# power_board.net
KiCad netlist of a schematic drawn in EAGLE
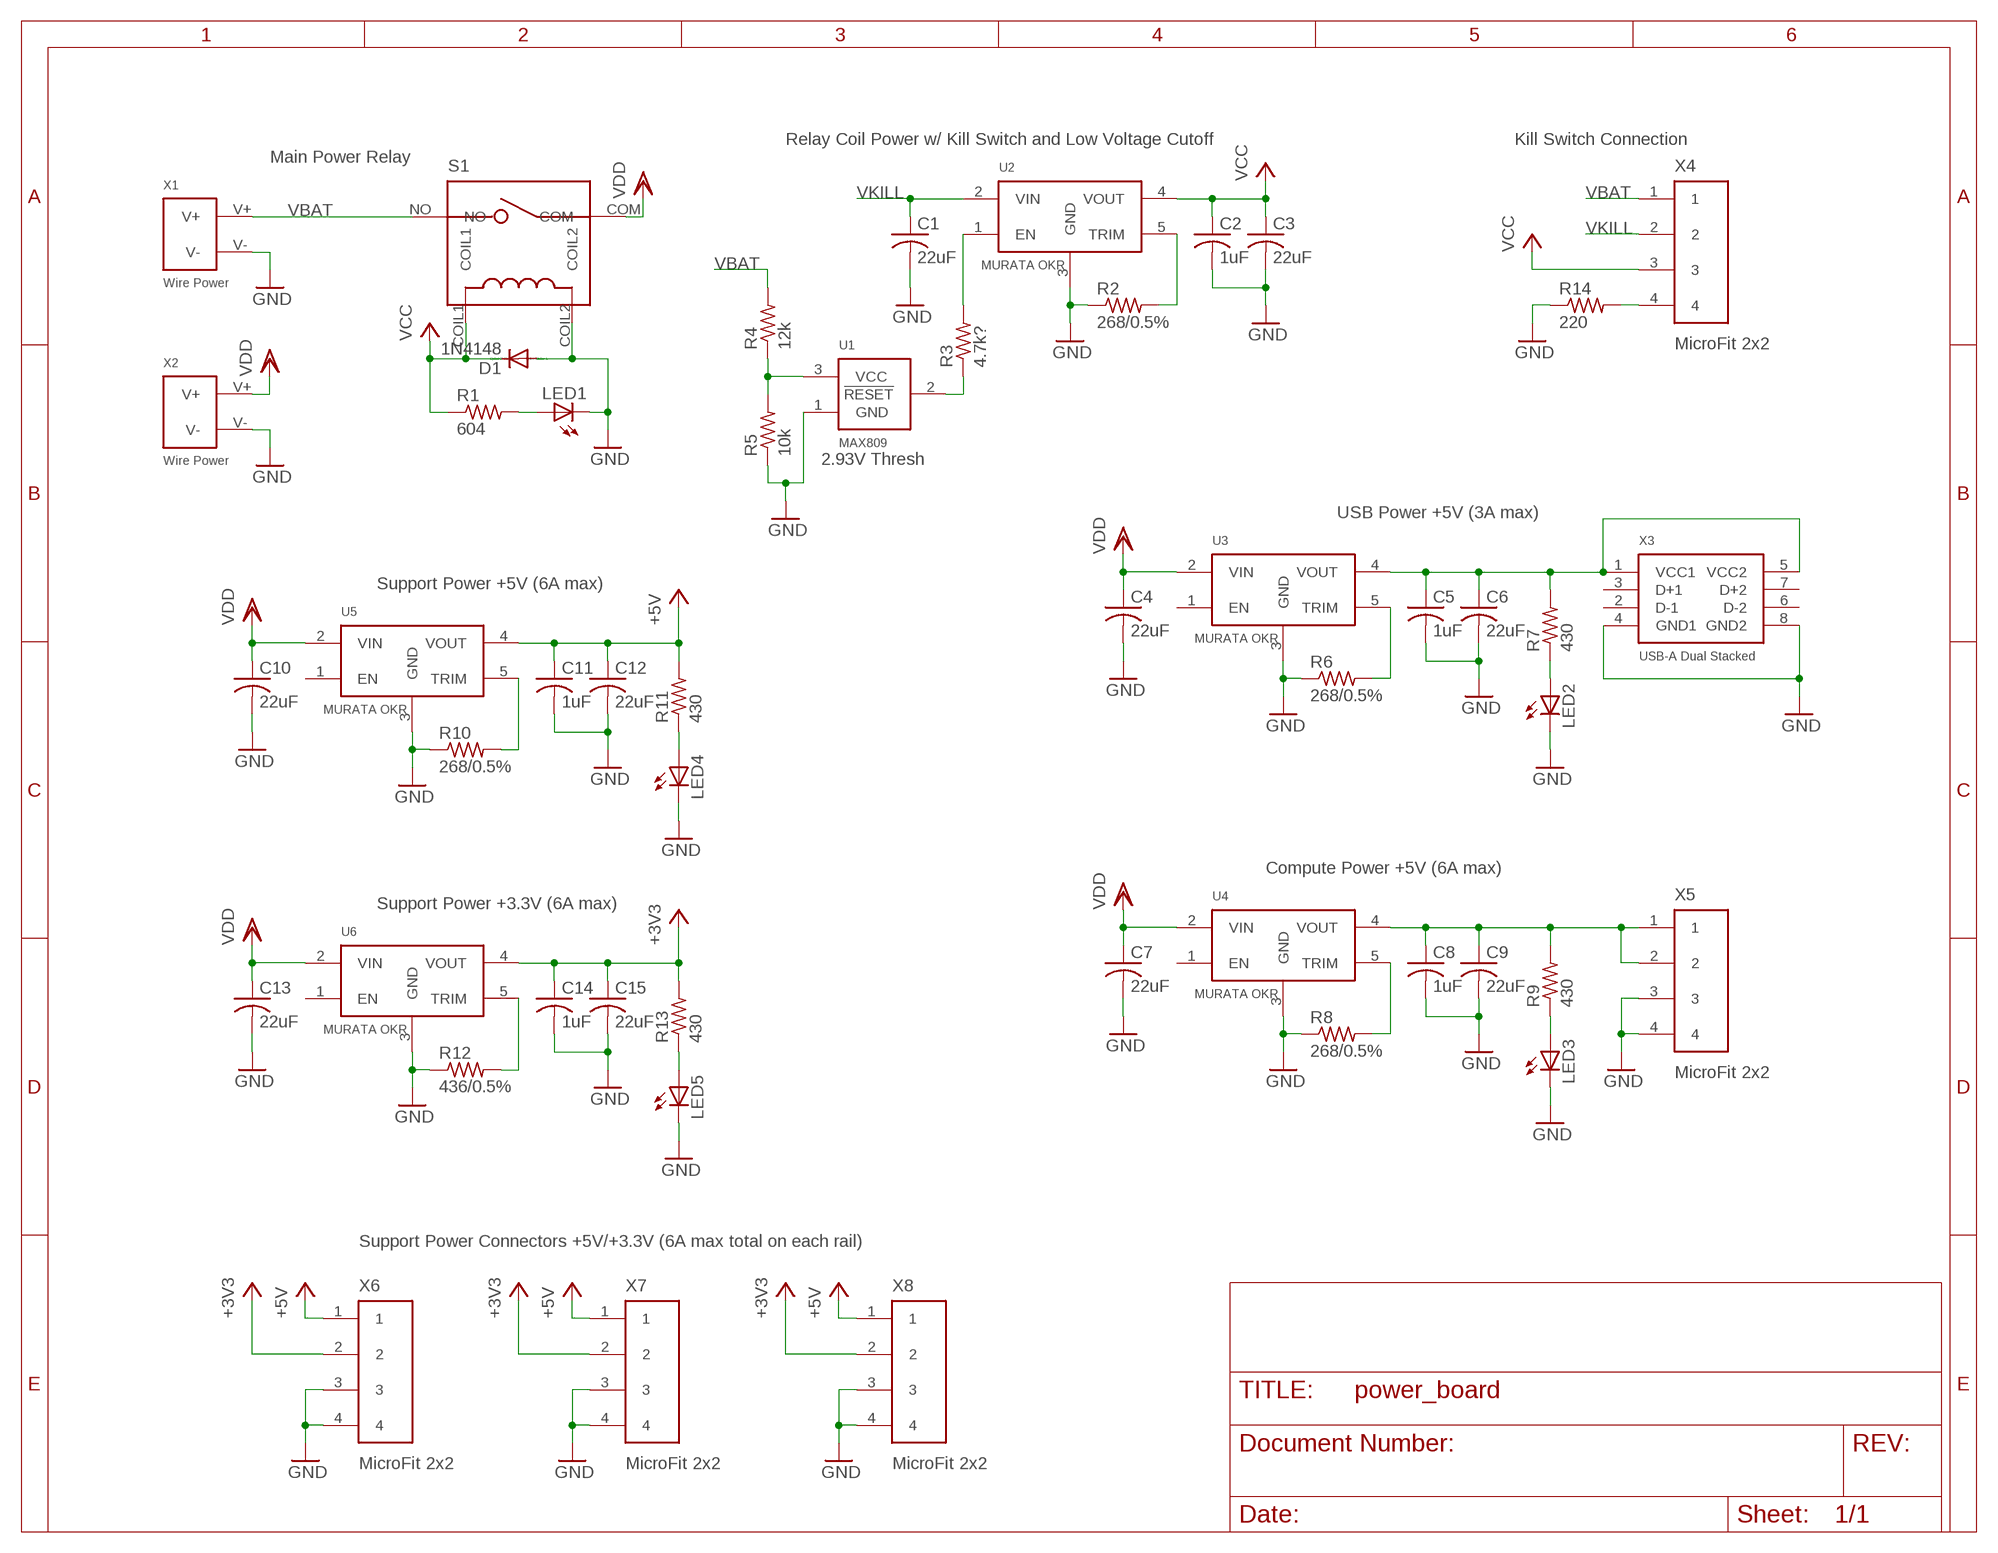
[diagram p0: schematic, sheet 1]

(export (version "E")
  (design (tool "Eeschema 10.0.6"))
  (components
    (comp (ref "C1")
      (value "22uF")
      (footprint "eagle-import:C1210")
      (libsource (lib "eagle-import") (part "C-USC1210"))
    )
    (comp (ref "C2")
      (value "1uF")
      (footprint "eagle-import:C1210")
      (libsource (lib "eagle-import") (part "C-USC1210"))
    )
    (comp (ref "C3")
      (value "22uF")
      (footprint "eagle-import:C1210")
      (libsource (lib "eagle-import") (part "C-USC1210"))
    )
    (comp (ref "C4")
      (value "22uF")
      (footprint "eagle-import:C1210")
      (libsource (lib "eagle-import") (part "C-USC1210"))
    )
    (comp (ref "C5")
      (value "1uF")
      (footprint "eagle-import:C1210")
      (libsource (lib "eagle-import") (part "C-USC1210"))
    )
    (comp (ref "C6")
      (value "22uF")
      (footprint "eagle-import:C1210")
      (libsource (lib "eagle-import") (part "C-USC1210"))
    )
    (comp (ref "C7")
      (value "22uF")
      (footprint "eagle-import:C1210")
      (libsource (lib "eagle-import") (part "C-USC1210"))
    )
    (comp (ref "C8")
      (value "1uF")
      (footprint "eagle-import:C1210")
      (libsource (lib "eagle-import") (part "C-USC1210"))
    )
    (comp (ref "C9")
      (value "22uF")
      (footprint "eagle-import:C1210")
      (libsource (lib "eagle-import") (part "C-USC1210"))
    )
    (comp (ref "C10")
      (value "22uF")
      (footprint "eagle-import:C1210")
      (libsource (lib "eagle-import") (part "C-USC1210"))
    )
    (comp (ref "C11")
      (value "1uF")
      (footprint "eagle-import:C1210")
      (libsource (lib "eagle-import") (part "C-USC1210"))
    )
    (comp (ref "C12")
      (value "22uF")
      (footprint "eagle-import:C1210")
      (libsource (lib "eagle-import") (part "C-USC1210"))
    )
    (comp (ref "C13")
      (value "22uF")
      (footprint "eagle-import:C1210")
      (libsource (lib "eagle-import") (part "C-USC1210"))
    )
    (comp (ref "C14")
      (value "1uF")
      (footprint "eagle-import:C1210")
      (libsource (lib "eagle-import") (part "C-USC1210"))
    )
    (comp (ref "C15")
      (value "22uF")
      (footprint "eagle-import:C1210")
      (libsource (lib "eagle-import") (part "C-USC1210"))
    )
    (comp (ref "D1")
      (value "1N4148")
      (footprint "eagle-import:SOD123")
      (libsource (lib "eagle-import") (part "DIODE-SOD123"))
    )
    (comp (ref "LED1")
      (value "LEDCHIPLED_0603")
      (footprint "eagle-import:CHIPLED_0603")
      (libsource (lib "eagle-import") (part "LEDCHIPLED_0603"))
    )
    (comp (ref "LED2")
      (value "LEDCHIPLED_0603")
      (footprint "eagle-import:CHIPLED_0603")
      (libsource (lib "eagle-import") (part "LEDCHIPLED_0603"))
    )
    (comp (ref "LED3")
      (value "LEDCHIPLED_0603")
      (footprint "eagle-import:CHIPLED_0603")
      (libsource (lib "eagle-import") (part "LEDCHIPLED_0603"))
    )
    (comp (ref "LED4")
      (value "LEDCHIPLED_0603")
      (footprint "eagle-import:CHIPLED_0603")
      (libsource (lib "eagle-import") (part "LEDCHIPLED_0603"))
    )
    (comp (ref "LED5")
      (value "LEDCHIPLED_0603")
      (footprint "eagle-import:CHIPLED_0603")
      (libsource (lib "eagle-import") (part "LEDCHIPLED_0603"))
    )
    (comp (ref "R1")
      (value "604")
      (footprint "eagle-import:R0603")
      (libsource (lib "eagle-import") (part "R-US_R0603"))
    )
    (comp (ref "R2")
      (value "268/0.5%")
      (footprint "eagle-import:R0603")
      (libsource (lib "eagle-import") (part "R-US_R0603"))
    )
    (comp (ref "R3")
      (value "4.7k?")
      (footprint "eagle-import:R0603")
      (libsource (lib "eagle-import") (part "R-US_R0603"))
    )
    (comp (ref "R4")
      (value "12k")
      (footprint "eagle-import:R0603")
      (libsource (lib "eagle-import") (part "R-US_R0603"))
    )
    (comp (ref "R5")
      (value "10k")
      (footprint "eagle-import:R0603")
      (libsource (lib "eagle-import") (part "R-US_R0603"))
    )
    (comp (ref "R6")
      (value "268/0.5%")
      (footprint "eagle-import:R0603")
      (libsource (lib "eagle-import") (part "R-US_R0603"))
    )
    (comp (ref "R7")
      (value "430")
      (footprint "eagle-import:R0603")
      (libsource (lib "eagle-import") (part "R-US_R0603"))
    )
    (comp (ref "R8")
      (value "268/0.5%")
      (footprint "eagle-import:R0603")
      (libsource (lib "eagle-import") (part "R-US_R0603"))
    )
    (comp (ref "R9")
      (value "430")
      (footprint "eagle-import:R0603")
      (libsource (lib "eagle-import") (part "R-US_R0603"))
    )
    (comp (ref "R10")
      (value "268/0.5%")
      (footprint "eagle-import:R0603")
      (libsource (lib "eagle-import") (part "R-US_R0603"))
    )
    (comp (ref "R11")
      (value "430")
      (footprint "eagle-import:R0603")
      (libsource (lib "eagle-import") (part "R-US_R0603"))
    )
    (comp (ref "R12")
      (value "436/0.5%")
      (footprint "eagle-import:R0603")
      (libsource (lib "eagle-import") (part "R-US_R0603"))
    )
    (comp (ref "R13")
      (value "430")
      (footprint "eagle-import:R0603")
      (libsource (lib "eagle-import") (part "R-US_R0603"))
    )
    (comp (ref "R14")
      (value "220")
      (footprint "eagle-import:R0603")
      (libsource (lib "eagle-import") (part "R-US_R0603"))
    )
    (comp (ref "S1")
      (value "T90S1D12-5")
      (footprint "eagle-import:T90S1D12-5")
      (libsource (lib "eagle-import") (part "T90S1D12-5"))
    )
    (comp (ref "U1")
      (value "MAX809")
      (footprint "eagle-import:SOT-23")
      (libsource (lib "eagle-import") (part "MAX809"))
    )
    (comp (ref "U2")
      (value "MURATA-OKR")
      (footprint "eagle-import:MURATA-OKR")
      (libsource (lib "eagle-import") (part "MURATA-OKR"))
    )
    (comp (ref "U3")
      (value "MURATA-OKR")
      (footprint "eagle-import:MURATA-OKR")
      (libsource (lib "eagle-import") (part "MURATA-OKR"))
    )
    (comp (ref "U4")
      (value "MURATA-OKR")
      (footprint "eagle-import:MURATA-OKR")
      (libsource (lib "eagle-import") (part "MURATA-OKR"))
    )
    (comp (ref "U5")
      (value "MURATA-OKR")
      (footprint "eagle-import:MURATA-OKR")
      (libsource (lib "eagle-import") (part "MURATA-OKR"))
    )
    (comp (ref "U6")
      (value "MURATA-OKR")
      (footprint "eagle-import:MURATA-OKR")
      (libsource (lib "eagle-import") (part "MURATA-OKR"))
    )
    (comp (ref "X1")
      (value "WIRE-POWER")
      (footprint "eagle-import:WIRE-POWER")
      (libsource (lib "eagle-import") (part "WIRE-POWER"))
    )
    (comp (ref "X2")
      (value "WIRE-POWER")
      (footprint "eagle-import:WIRE-POWER")
      (libsource (lib "eagle-import") (part "WIRE-POWER"))
    )
    (comp (ref "X3")
      (value "USB-A-STACKED")
      (footprint "eagle-import:USB-A-STACKED")
      (libsource (lib "eagle-import") (part "USB-A-STACKED"))
    )
    (comp (ref "X4")
      (value "MICROFIT-2X2-SMD")
      (footprint "eagle-import:MICROFIT-2X2-0430450411")
      (libsource (lib "eagle-import") (part "MICROFIT-2X2-SMD"))
    )
    (comp (ref "X5")
      (value "MICROFIT-2X2-SMD")
      (footprint "eagle-import:MICROFIT-2X2-0430450411")
      (libsource (lib "eagle-import") (part "MICROFIT-2X2-SMD"))
    )
    (comp (ref "X6")
      (value "MICROFIT-2X2-SMD")
      (footprint "eagle-import:MICROFIT-2X2-0430450411")
      (libsource (lib "eagle-import") (part "MICROFIT-2X2-SMD"))
    )
    (comp (ref "X7")
      (value "MICROFIT-2X2-SMD")
      (footprint "eagle-import:MICROFIT-2X2-0430450411")
      (libsource (lib "eagle-import") (part "MICROFIT-2X2-SMD"))
    )
    (comp (ref "X8")
      (value "MICROFIT-2X2-SMD")
      (footprint "eagle-import:MICROFIT-2X2-0430450411")
      (libsource (lib "eagle-import") (part "MICROFIT-2X2-SMD"))
    )
  )
  (nets
    (net (code "1") (name "+3V3") (class "Default")
      (node (ref "C14") (pin "1") (pinfunction "1_1") (pintype "passive"))
      (node (ref "C15") (pin "1") (pinfunction "1_1") (pintype "passive"))
      (node (ref "R13") (pin "2") (pinfunction "2_2") (pintype "passive"))
      (node (ref "U6") (pin "4") (pinfunction "VOUT_4") (pintype "power_in"))
      (node (ref "X6") (pin "2") (pinfunction "2_2") (pintype "bidirectional"))
      (node (ref "X7") (pin "2") (pinfunction "2_2") (pintype "bidirectional"))
      (node (ref "X8") (pin "2") (pinfunction "2_2") (pintype "bidirectional"))
    )
    (net (code "2") (name "+5V") (class "Default")
      (node (ref "C11") (pin "1") (pinfunction "1_1") (pintype "passive"))
      (node (ref "C12") (pin "1") (pinfunction "1_1") (pintype "passive"))
      (node (ref "R11") (pin "2") (pinfunction "2_2") (pintype "passive"))
      (node (ref "U5") (pin "4") (pinfunction "VOUT_4") (pintype "power_in"))
      (node (ref "X6") (pin "1") (pinfunction "1_1") (pintype "bidirectional"))
      (node (ref "X7") (pin "1") (pinfunction "1_1") (pintype "bidirectional"))
      (node (ref "X8") (pin "1") (pinfunction "1_1") (pintype "bidirectional"))
    )
    (net (code "3") (name "/VBAT") (class "Default")
      (node (ref "R4") (pin "2") (pinfunction "2_2") (pintype "passive"))
      (node (ref "S1") (pin "NO") (pinfunction "NO_NO") (pintype "power_in"))
      (node (ref "X1") (pin "V+") (pinfunction "V+_V+") (pintype "power_in"))
      (node (ref "X4") (pin "1") (pinfunction "1_1") (pintype "bidirectional"))
    )
    (net (code "4") (name "/VKILL") (class "Default")
      (node (ref "C1") (pin "1") (pinfunction "1_1") (pintype "passive"))
      (node (ref "U2") (pin "2") (pinfunction "VIN_2") (pintype "power_in"))
      (node (ref "X4") (pin "2") (pinfunction "2_2") (pintype "bidirectional"))
    )
    (net (code "5") (name "GND") (class "Default")
      (node (ref "C1") (pin "2") (pinfunction "2_2") (pintype "passive"))
      (node (ref "C10") (pin "2") (pinfunction "2_2") (pintype "passive"))
      (node (ref "C11") (pin "2") (pinfunction "2_2") (pintype "passive"))
      (node (ref "C12") (pin "2") (pinfunction "2_2") (pintype "passive"))
      (node (ref "C13") (pin "2") (pinfunction "2_2") (pintype "passive"))
      (node (ref "C14") (pin "2") (pinfunction "2_2") (pintype "passive"))
      (node (ref "C15") (pin "2") (pinfunction "2_2") (pintype "passive"))
      (node (ref "C2") (pin "2") (pinfunction "2_2") (pintype "passive"))
      (node (ref "C3") (pin "2") (pinfunction "2_2") (pintype "passive"))
      (node (ref "C4") (pin "2") (pinfunction "2_2") (pintype "passive"))
      (node (ref "C5") (pin "2") (pinfunction "2_2") (pintype "passive"))
      (node (ref "C6") (pin "2") (pinfunction "2_2") (pintype "passive"))
      (node (ref "C7") (pin "2") (pinfunction "2_2") (pintype "passive"))
      (node (ref "C8") (pin "2") (pinfunction "2_2") (pintype "passive"))
      (node (ref "C9") (pin "2") (pinfunction "2_2") (pintype "passive"))
      (node (ref "D1") (pin "A") (pinfunction "A_A") (pintype "passive"))
      (node (ref "LED1") (pin "C") (pinfunction "C_C") (pintype "passive"))
      (node (ref "LED2") (pin "C") (pinfunction "C_C") (pintype "passive"))
      (node (ref "LED3") (pin "C") (pinfunction "C_C") (pintype "passive"))
      (node (ref "LED4") (pin "C") (pinfunction "C_C") (pintype "passive"))
      (node (ref "LED5") (pin "C") (pinfunction "C_C") (pintype "passive"))
      (node (ref "R10") (pin "1") (pinfunction "1_1") (pintype "passive"))
      (node (ref "R12") (pin "1") (pinfunction "1_1") (pintype "passive"))
      (node (ref "R14") (pin "1") (pinfunction "1_1") (pintype "passive"))
      (node (ref "R2") (pin "1") (pinfunction "1_1") (pintype "passive"))
      (node (ref "R5") (pin "1") (pinfunction "1_1") (pintype "passive"))
      (node (ref "R6") (pin "1") (pinfunction "1_1") (pintype "passive"))
      (node (ref "R8") (pin "1") (pinfunction "1_1") (pintype "passive"))
      (node (ref "S1") (pin "COIL2") (pinfunction "COIL2_COIL2") (pintype "bidirectional"))
      (node (ref "U1") (pin "1") (pinfunction "GND_1") (pintype "power_in"))
      (node (ref "U2") (pin "3") (pinfunction "GND_3") (pintype "power_in"))
      (node (ref "U3") (pin "3") (pinfunction "GND_3") (pintype "power_in"))
      (node (ref "U4") (pin "3") (pinfunction "GND_3") (pintype "power_in"))
      (node (ref "U5") (pin "3") (pinfunction "GND_3") (pintype "power_in"))
      (node (ref "U6") (pin "3") (pinfunction "GND_3") (pintype "power_in"))
      (node (ref "X1") (pin "V-") (pinfunction "V-_V-") (pintype "power_in"))
      (node (ref "X2") (pin "V-") (pinfunction "V-_V-") (pintype "power_in"))
      (node (ref "X3") (pin "4") (pinfunction "GND1_4") (pintype "power_in"))
      (node (ref "X3") (pin "8") (pinfunction "GND2_8") (pintype "power_in"))
      (node (ref "X5") (pin "3") (pinfunction "3_3") (pintype "bidirectional"))
      (node (ref "X5") (pin "4") (pinfunction "4_4") (pintype "bidirectional"))
      (node (ref "X6") (pin "3") (pinfunction "3_3") (pintype "bidirectional"))
      (node (ref "X6") (pin "4") (pinfunction "4_4") (pintype "bidirectional"))
      (node (ref "X7") (pin "3") (pinfunction "3_3") (pintype "bidirectional"))
      (node (ref "X7") (pin "4") (pinfunction "4_4") (pintype "bidirectional"))
      (node (ref "X8") (pin "3") (pinfunction "3_3") (pintype "bidirectional"))
      (node (ref "X8") (pin "4") (pinfunction "4_4") (pintype "bidirectional"))
    )
    (net (code "6") (name "Net-(LED1-PadA)") (class "Default")
      (node (ref "LED1") (pin "A") (pinfunction "A_A") (pintype "passive"))
      (node (ref "R1") (pin "2") (pinfunction "2_2") (pintype "passive"))
    )
    (net (code "7") (name "Net-(LED2-PadA)") (class "Default")
      (node (ref "LED2") (pin "A") (pinfunction "A_A") (pintype "passive"))
      (node (ref "R7") (pin "1") (pinfunction "1_1") (pintype "passive"))
    )
    (net (code "8") (name "Net-(LED3-PadA)") (class "Default")
      (node (ref "LED3") (pin "A") (pinfunction "A_A") (pintype "passive"))
      (node (ref "R9") (pin "1") (pinfunction "1_1") (pintype "passive"))
    )
    (net (code "9") (name "Net-(LED4-PadA)") (class "Default")
      (node (ref "LED4") (pin "A") (pinfunction "A_A") (pintype "passive"))
      (node (ref "R11") (pin "1") (pinfunction "1_1") (pintype "passive"))
    )
    (net (code "10") (name "Net-(LED5-PadA)") (class "Default")
      (node (ref "LED5") (pin "A") (pinfunction "A_A") (pintype "passive"))
      (node (ref "R13") (pin "1") (pinfunction "1_1") (pintype "passive"))
    )
    (net (code "11") (name "Net-(R14-Pad2)") (class "Default")
      (node (ref "R14") (pin "2") (pinfunction "2_2") (pintype "passive"))
      (node (ref "X4") (pin "4") (pinfunction "4_4") (pintype "bidirectional"))
    )
    (net (code "12") (name "Net-(U1-VCC)") (class "Default")
      (node (ref "R4") (pin "1") (pinfunction "1_1") (pintype "passive"))
      (node (ref "R5") (pin "2") (pinfunction "2_2") (pintype "passive"))
      (node (ref "U1") (pin "3") (pinfunction "VCC_3") (pintype "power_in"))
    )
    (net (code "13") (name "Net-(U1-~{RESET})") (class "Default")
      (node (ref "R3") (pin "1") (pinfunction "1_1") (pintype "passive"))
      (node (ref "U1") (pin "2") (pinfunction "~{RESET}_2") (pintype "bidirectional"))
    )
    (net (code "14") (name "Net-(U2-EN)") (class "Default")
      (node (ref "R3") (pin "2") (pinfunction "2_2") (pintype "passive"))
      (node (ref "U2") (pin "1") (pinfunction "EN_1") (pintype "bidirectional"))
    )
    (net (code "15") (name "Net-(U2-TRIM)") (class "Default")
      (node (ref "R2") (pin "2") (pinfunction "2_2") (pintype "passive"))
      (node (ref "U2") (pin "5") (pinfunction "TRIM_5") (pintype "bidirectional"))
    )
    (net (code "16") (name "Net-(U3-TRIM)") (class "Default")
      (node (ref "R6") (pin "2") (pinfunction "2_2") (pintype "passive"))
      (node (ref "U3") (pin "5") (pinfunction "TRIM_5") (pintype "bidirectional"))
    )
    (net (code "17") (name "Net-(U3-VOUT)") (class "Default")
      (node (ref "C5") (pin "1") (pinfunction "1_1") (pintype "passive"))
      (node (ref "C6") (pin "1") (pinfunction "1_1") (pintype "passive"))
      (node (ref "R7") (pin "2") (pinfunction "2_2") (pintype "passive"))
      (node (ref "U3") (pin "4") (pinfunction "VOUT_4") (pintype "power_in"))
      (node (ref "X3") (pin "1") (pinfunction "VCC1_1") (pintype "power_in"))
      (node (ref "X3") (pin "5") (pinfunction "VCC2_5") (pintype "power_in"))
    )
    (net (code "18") (name "Net-(U4-TRIM)") (class "Default")
      (node (ref "R8") (pin "2") (pinfunction "2_2") (pintype "passive"))
      (node (ref "U4") (pin "5") (pinfunction "TRIM_5") (pintype "bidirectional"))
    )
    (net (code "19") (name "Net-(U4-VOUT)") (class "Default")
      (node (ref "C8") (pin "1") (pinfunction "1_1") (pintype "passive"))
      (node (ref "C9") (pin "1") (pinfunction "1_1") (pintype "passive"))
      (node (ref "R9") (pin "2") (pinfunction "2_2") (pintype "passive"))
      (node (ref "U4") (pin "4") (pinfunction "VOUT_4") (pintype "power_in"))
      (node (ref "X5") (pin "1") (pinfunction "1_1") (pintype "bidirectional"))
      (node (ref "X5") (pin "2") (pinfunction "2_2") (pintype "bidirectional"))
    )
    (net (code "20") (name "Net-(U5-TRIM)") (class "Default")
      (node (ref "R10") (pin "2") (pinfunction "2_2") (pintype "passive"))
      (node (ref "U5") (pin "5") (pinfunction "TRIM_5") (pintype "bidirectional"))
    )
    (net (code "21") (name "Net-(U6-TRIM)") (class "Default")
      (node (ref "R12") (pin "2") (pinfunction "2_2") (pintype "passive"))
      (node (ref "U6") (pin "5") (pinfunction "TRIM_5") (pintype "bidirectional"))
    )
    (net (code "22") (name "VCC") (class "Default")
      (node (ref "C2") (pin "1") (pinfunction "1_1") (pintype "passive"))
      (node (ref "C3") (pin "1") (pinfunction "1_1") (pintype "passive"))
      (node (ref "D1") (pin "C") (pinfunction "C_C") (pintype "passive"))
      (node (ref "R1") (pin "1") (pinfunction "1_1") (pintype "passive"))
      (node (ref "S1") (pin "COIL1") (pinfunction "COIL1_COIL1") (pintype "bidirectional"))
      (node (ref "U2") (pin "4") (pinfunction "VOUT_4") (pintype "power_in"))
      (node (ref "X4") (pin "3") (pinfunction "3_3") (pintype "bidirectional"))
    )
    (net (code "23") (name "VDD") (class "Default")
      (node (ref "C10") (pin "1") (pinfunction "1_1") (pintype "passive"))
      (node (ref "C13") (pin "1") (pinfunction "1_1") (pintype "passive"))
      (node (ref "C4") (pin "1") (pinfunction "1_1") (pintype "passive"))
      (node (ref "C7") (pin "1") (pinfunction "1_1") (pintype "passive"))
      (node (ref "S1") (pin "COM") (pinfunction "COM_COM") (pintype "power_in"))
      (node (ref "U3") (pin "2") (pinfunction "VIN_2") (pintype "power_in"))
      (node (ref "U4") (pin "2") (pinfunction "VIN_2") (pintype "power_in"))
      (node (ref "U5") (pin "2") (pinfunction "VIN_2") (pintype "power_in"))
      (node (ref "U6") (pin "2") (pinfunction "VIN_2") (pintype "power_in"))
      (node (ref "X2") (pin "V+") (pinfunction "V+_V+") (pintype "power_in"))
    )
    (net (code "24") (name "unconnected-(U3-EN-Pad1)") (class "Default")
      (node (ref "U3") (pin "1") (pinfunction "EN_1") (pintype "bidirectional"))
    )
    (net (code "25") (name "unconnected-(U4-EN-Pad1)") (class "Default")
      (node (ref "U4") (pin "1") (pinfunction "EN_1") (pintype "bidirectional"))
    )
    (net (code "26") (name "unconnected-(U5-EN-Pad1)") (class "Default")
      (node (ref "U5") (pin "1") (pinfunction "EN_1") (pintype "bidirectional"))
    )
    (net (code "27") (name "unconnected-(U6-EN-Pad1)") (class "Default")
      (node (ref "U6") (pin "1") (pinfunction "EN_1") (pintype "bidirectional"))
    )
    (net (code "28") (name "unconnected-(X3-D+1-Pad3)") (class "Default")
      (node (ref "X3") (pin "3") (pinfunction "D+1_3") (pintype "bidirectional"))
    )
    (net (code "29") (name "unconnected-(X3-D+2-Pad7)") (class "Default")
      (node (ref "X3") (pin "7") (pinfunction "D+2_7") (pintype "bidirectional"))
    )
    (net (code "30") (name "unconnected-(X3-D-1-Pad2)") (class "Default")
      (node (ref "X3") (pin "2") (pinfunction "D-1_2") (pintype "bidirectional"))
    )
    (net (code "31") (name "unconnected-(X3-D-2-Pad6)") (class "Default")
      (node (ref "X3") (pin "6") (pinfunction "D-2_6") (pintype "bidirectional"))
    )
  )
)
